# HHT_CAL_PWR_3_1_20170407.net
KiCad netlist of a schematic drawn in Altium Designer
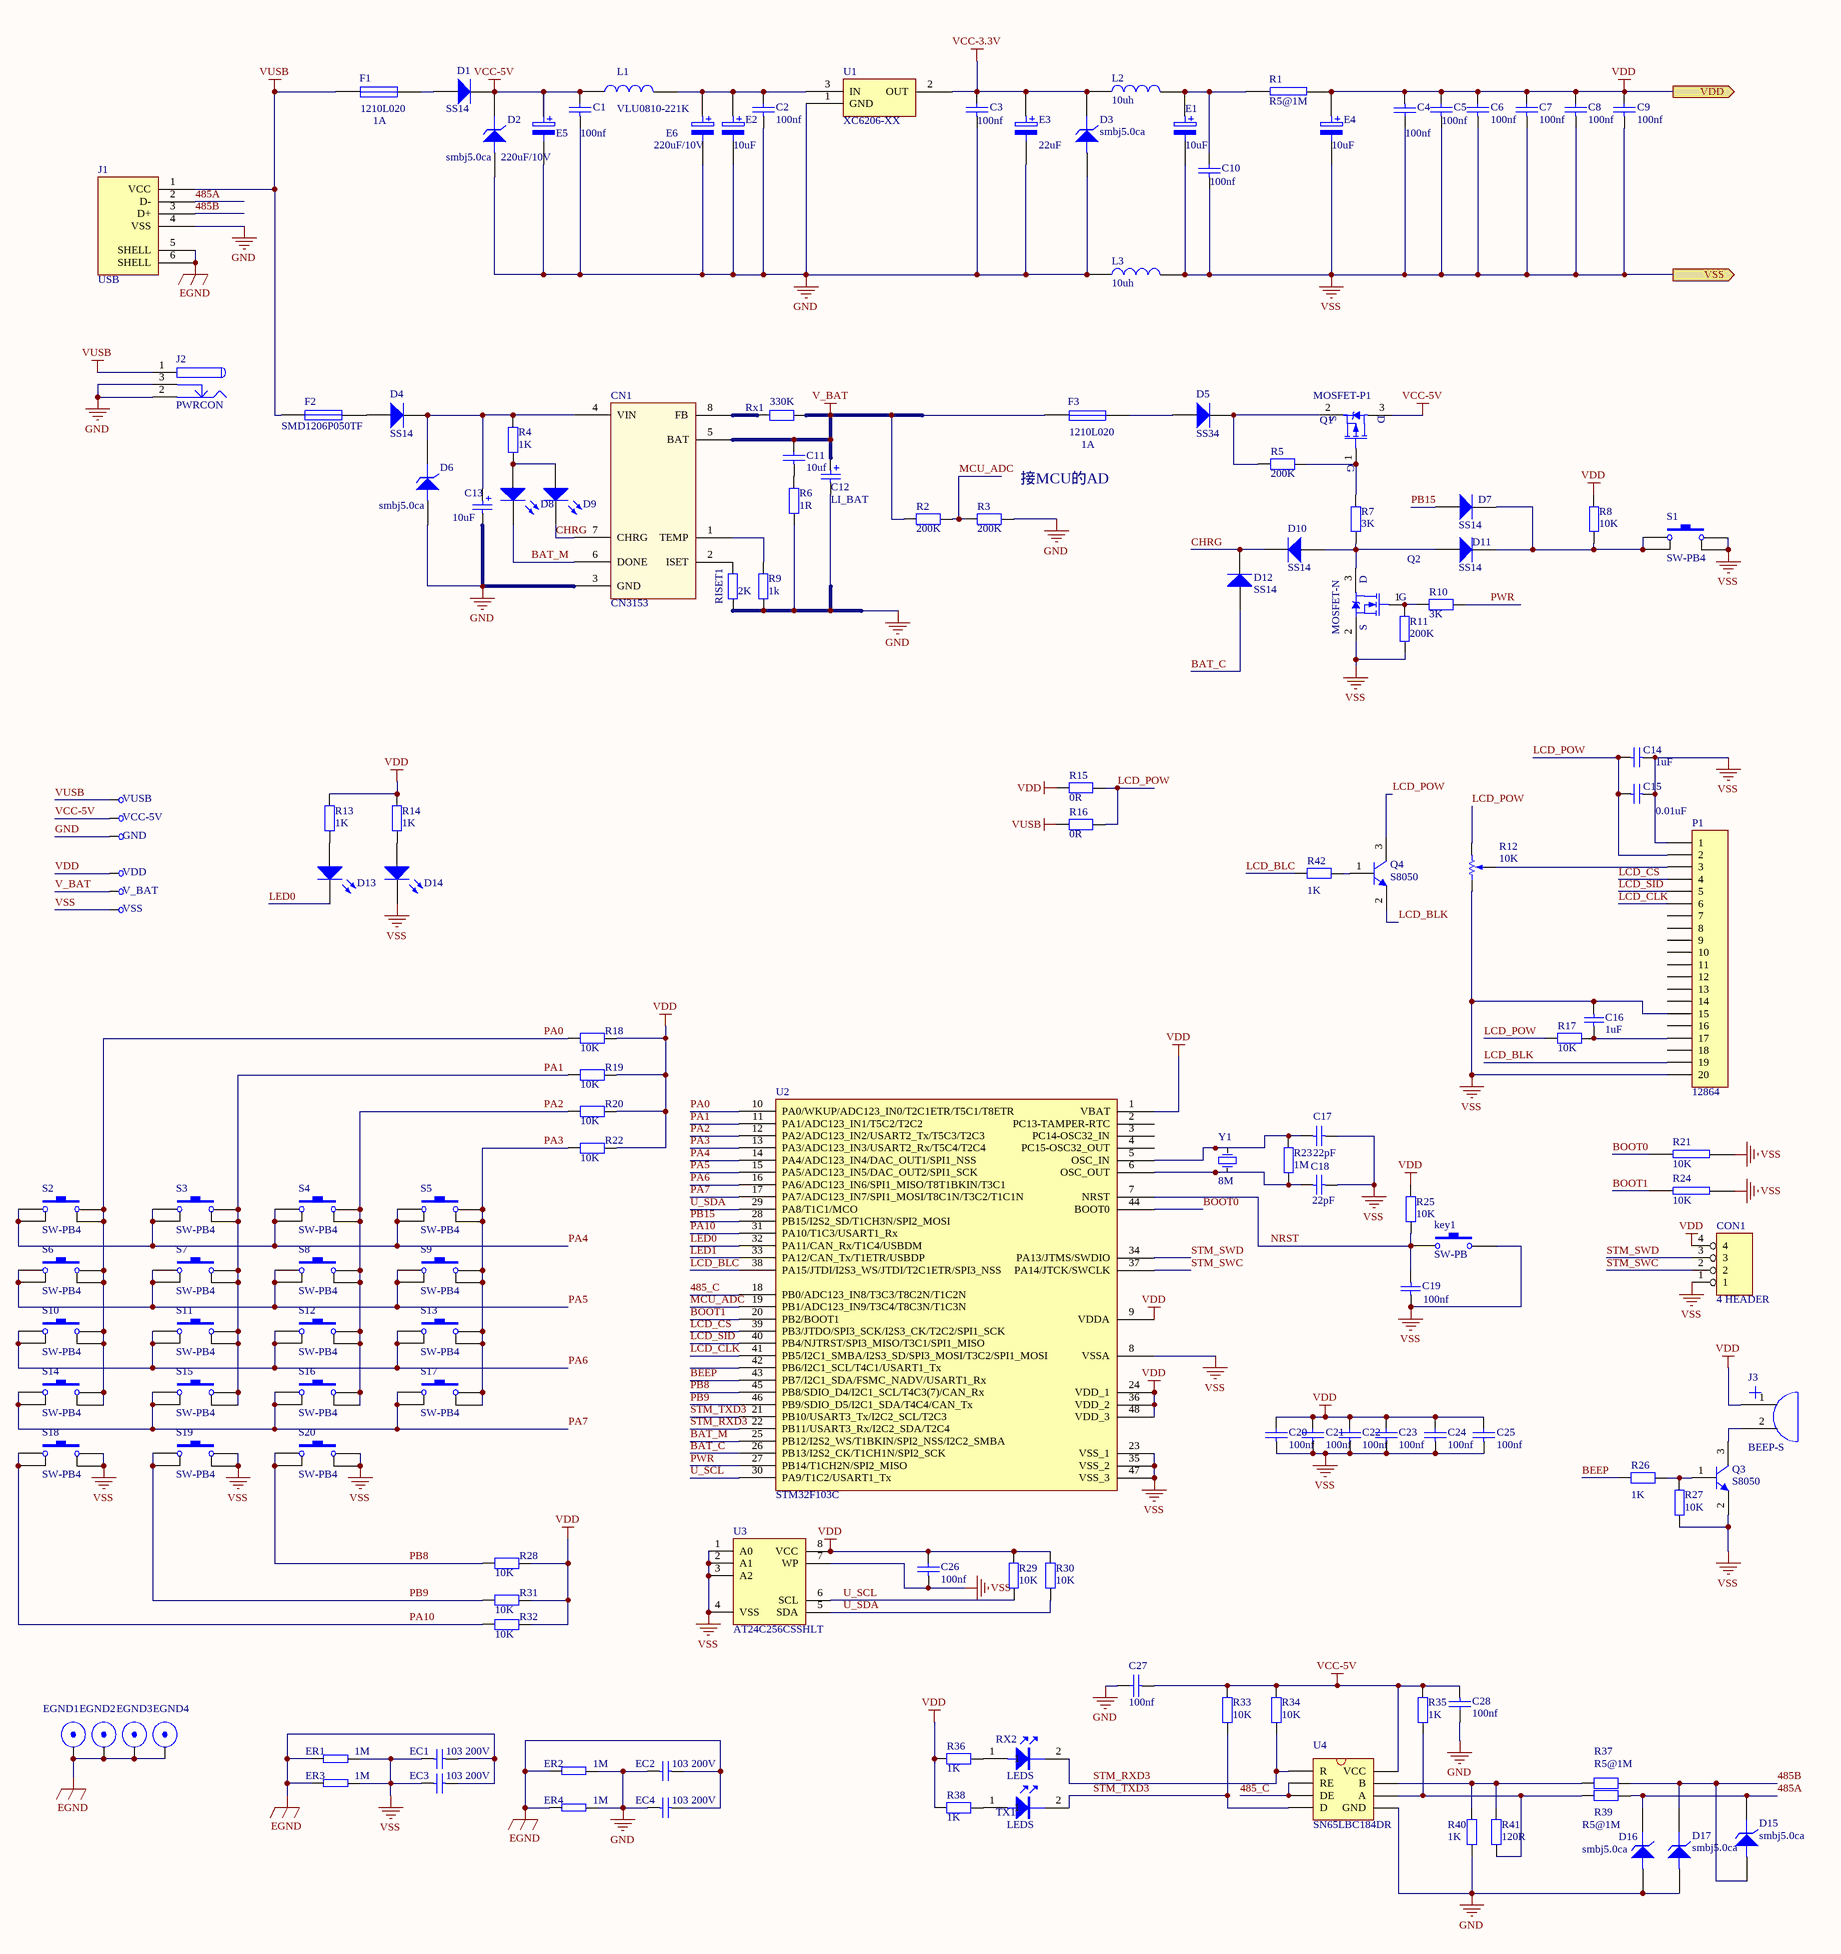
[diagram p0: HHT_CAL_PWR_3.1_20170407.SchDoc]

(export (version "E")
  (design (tool "Eeschema 10.0.6"))
  (components
    (comp (ref "C1")
      (value "100nf")
      (footprint "LC-0805_C")
      (description "Capacitor")
      (libsource (lib "Miscellaneous Devices") (part "CAP"))
    )
    (comp (ref "C2")
      (value "100nf")
      (footprint "LC-0603_C")
      (description "Capacitor")
      (libsource (lib "Miscellaneous Devices") (part "CAP"))
    )
    (comp (ref "C3")
      (value "100nf")
      (footprint "LC-0603_C")
      (description "Capacitor")
      (libsource (lib "Miscellaneous Devices") (part "CAP"))
    )
    (comp (ref "C4")
      (value "100nf")
      (footprint "LC-0603_C")
      (description "Capacitor")
      (libsource (lib "Miscellaneous Devices") (part "CAP"))
    )
    (comp (ref "C5")
      (value "100nf")
      (footprint "LC-0603_C")
      (description "Capacitor")
      (libsource (lib "Miscellaneous Devices") (part "CAP"))
    )
    (comp (ref "C6")
      (value "100nf")
      (footprint "LC-0603_C")
      (description "Capacitor")
      (libsource (lib "Miscellaneous Devices") (part "CAP"))
    )
    (comp (ref "C7")
      (value "100nf")
      (footprint "LC-0603_C")
      (description "Capacitor")
      (libsource (lib "Miscellaneous Devices") (part "CAP"))
    )
    (comp (ref "C8")
      (value "100nf")
      (footprint "LC-0603_C")
      (description "Capacitor")
      (libsource (lib "Miscellaneous Devices") (part "CAP"))
    )
    (comp (ref "C9")
      (value "100nf")
      (footprint "LC-0603_C")
      (description "Capacitor")
      (libsource (lib "Miscellaneous Devices") (part "CAP"))
    )
    (comp (ref "C10")
      (value "100nf")
      (footprint "LC-0603_C")
      (description "Capacitor")
      (libsource (lib "Miscellaneous Devices") (part "CAP"))
    )
    (comp (ref "C11")
      (value "10uf")
      (footprint "LC-CASE-A_3216")
      (description "Capacitor")
      (libsource (lib "Miscellaneous Devices") (part "CAP"))
    )
    (comp (ref "C12")
      (value "LI_BAT")
      (footprint "HDR2X1-2.54")
      (description "Polarized Capacitor (Radial)")
      (fields (field (name "PUBLISHER") "Altium Limited"))
      (libsource (lib "Miscellaneous Devices") (part "Cap Pol1"))
    )
    (comp (ref "C13")
      (value "10uF")
      (footprint "LC-CASE-B_3528")
      (description "Polarized Capacitor (Radial)")
      (fields (field (name "Comment") "100uF") (field (name "PUBLISHER") "Altium Limited"))
      (libsource (lib "Miscellaneous Devices") (part "Cap Pol1"))
    )
    (comp (ref "C14")
      (value "1uF")
      (footprint "LC-0603_C")
      (description "贴片瓷片电容")
      (fields (field (name "Comment") "1uf") (field (name "PUBLISHER") "Altium Limited"))
      (libsource (lib "fszhang") (part "Cap-S"))
    )
    (comp (ref "C15")
      (value "0.01uF")
      (footprint "LC-0603_C")
      (description "贴片瓷片电容")
      (fields (field (name "PUBLISHER") "Altium Limited"))
      (libsource (lib "fszhang") (part "Cap-S"))
    )
    (comp (ref "C16")
      (value "1uF")
      (footprint "LC-0603_C")
      (description "贴片瓷片电容")
      (fields (field (name "PUBLISHER") "Altium Limited"))
      (libsource (lib "fszhang") (part "Cap-S"))
    )
    (comp (ref "C17")
      (value "22pF")
      (footprint "LC-0603_C")
      (description "贴片瓷片电容")
      (fields (field (name "Comment") "22PF") (field (name "PUBLISHER") "Altium Limited"))
      (libsource (lib "fszhang") (part "Cap-S"))
    )
    (comp (ref "C18")
      (value "22pF")
      (footprint "LC-0603_C")
      (description "贴片瓷片电容")
      (fields (field (name "Comment") "22PF") (field (name "PUBLISHER") "Altium Limited"))
      (libsource (lib "fszhang") (part "Cap-S"))
    )
    (comp (ref "C19")
      (value "100nf")
      (footprint "LC-0603_C")
      (description "Capacitor")
      (fields (field (name "PUBLISHER") "Altium Limited"))
      (libsource (lib "Miscellaneous Devices") (part "Cap"))
    )
    (comp (ref "C20")
      (value "100nf")
      (footprint "LC-0603_C")
      (description "Capacitor")
      (libsource (lib "Miscellaneous Devices") (part "CAP"))
    )
    (comp (ref "C21")
      (value "100nf")
      (footprint "LC-0603_C")
      (description "Capacitor")
      (libsource (lib "Miscellaneous Devices") (part "CAP"))
    )
    (comp (ref "C22")
      (value "100nf")
      (footprint "LC-0603_C")
      (description "Capacitor")
      (libsource (lib "Miscellaneous Devices") (part "CAP"))
    )
    (comp (ref "C23")
      (value "100nf")
      (footprint "LC-0603_C")
      (description "Capacitor")
      (libsource (lib "Miscellaneous Devices") (part "CAP"))
    )
    (comp (ref "C24")
      (value "100nf")
      (footprint "LC-0603_C")
      (description "Capacitor")
      (libsource (lib "Miscellaneous Devices") (part "CAP"))
    )
    (comp (ref "C25")
      (value "100nf")
      (footprint "LC-0603_C")
      (description "Capacitor")
      (libsource (lib "Miscellaneous Devices") (part "CAP"))
    )
    (comp (ref "C26")
      (value "100nf")
      (footprint "LC-0603_C")
      (description "Capacitor")
      (libsource (lib "Miscellaneous Devices") (part "CAP"))
    )
    (comp (ref "C27")
      (value "100nf")
      (footprint "LC-0603_C")
      (description "Capacitor")
      (libsource (lib "Miscellaneous Devices") (part "CAP"))
    )
    (comp (ref "C28")
      (value "100nf")
      (footprint "LC-0603_C")
      (description "Capacitor")
      (libsource (lib "Miscellaneous Devices") (part "CAP"))
    )
    (comp (ref "CN1") (value "CN3153") (footprint "SOIC8") (libsource (lib "PCB_Project1") (part "CN3153")))
    (comp (ref "CON1")
      (value "4 HEADER")
      (footprint "sip4")
      (description "4 Pin Header")
      (libsource (lib "Miscellaneous Devices") (part "4 HEADER"))
    )
    (comp (ref "D1")
      (value "SS14")
      (footprint "LC-SMA(DO-214AC)_S5")
      (description "整流二极管")
      (fields (field (name "PUBLISHER") "Altium Limited"))
      (libsource (lib "fszhang") (part "Diode-R"))
    )
    (comp (ref "D2")
      (value "smbj5.0ca")
      (footprint "LC-SMB(DO-214AA)_S1")
      (description "Zener Diode")
      (libsource (lib "Miscellaneous Devices") (part "ZENER3"))
    )
    (comp (ref "D3")
      (value "smbj5.0ca")
      (footprint "LC-SMB(DO-214AA)_S1")
      (description "Zener Diode")
      (libsource (lib "Miscellaneous Devices") (part "ZENER3"))
    )
    (comp (ref "D4")
      (value "SS14")
      (footprint "LC-SMA(DO-214AC)_S5")
      (description "Default Diode")
      (fields (field (name "PUBLISHER") "Altium Limited"))
      (libsource (lib "Miscellaneous Devices") (part "Diode"))
    )
    (comp (ref "D5")
      (value "SS34")
      (footprint "LC-SMA(DO-214AC)_S5")
      (description "Default Diode")
      (fields (field (name "PUBLISHER") "Altium Limited"))
      (libsource (lib "Miscellaneous Devices") (part "Diode"))
    )
    (comp (ref "D6")
      (value "smbj5.0ca")
      (footprint "LC-SMA(DO-214AC)_S5")
      (description "Zener Diode")
      (libsource (lib "Miscellaneous Devices") (part "ZENER3"))
    )
    (comp (ref "D7")
      (value "SS14")
      (footprint "LC-SMA(DO-214AC)_S5")
      (description "Default Diode")
      (fields (field (name "PUBLISHER") "Altium Limited"))
      (libsource (lib "Miscellaneous Devices") (part "Diode"))
    )
    (comp (ref "D8")
      (value "LED0")
      (footprint "LED-0805")
      (description "发光二极管")
      (fields (field (name "PUBLISHER") "Altium Limited"))
      (libsource (lib "fszhang") (part "LED0"))
    )
    (comp (ref "D9")
      (value "LED0")
      (footprint "LED-0805")
      (description "发光二极管")
      (fields (field (name "PUBLISHER") "Altium Limited"))
      (libsource (lib "fszhang") (part "LED0"))
    )
    (comp (ref "D10")
      (value "SS14")
      (footprint "LC-SMA(DO-214AC)_S5")
      (description "Default Diode")
      (fields (field (name "PUBLISHER") "Altium Limited"))
      (libsource (lib "Miscellaneous Devices") (part "Diode"))
    )
    (comp (ref "D11")
      (value "SS14")
      (footprint "LC-SMA(DO-214AC)_S5")
      (description "Default Diode")
      (fields (field (name "PUBLISHER") "Altium Limited"))
      (libsource (lib "Miscellaneous Devices") (part "Diode"))
    )
    (comp (ref "D12")
      (value "SS14")
      (footprint "LC-SMA(DO-214AC)_S5")
      (description "Default Diode")
      (fields (field (name "PUBLISHER") "Altium Limited"))
      (libsource (lib "Miscellaneous Devices") (part "Diode"))
    )
    (comp (ref "D13")
      (value "LED0")
      (footprint "LC-0805_LED_S1")
      (description "发光二极管")
      (fields (field (name "PUBLISHER") "Altium Limited"))
      (libsource (lib "fszhang") (part "LED0"))
    )
    (comp (ref "D14")
      (value "LED0")
      (footprint "LC-0805_LED_S1")
      (description "发光二极管")
      (fields (field (name "PUBLISHER") "Altium Limited"))
      (libsource (lib "fszhang") (part "LED0"))
    )
    (comp (ref "D15")
      (value "smbj5.0ca")
      (footprint "LC-SMB(DO-214AA)_S1")
      (description "Zener Diode")
      (libsource (lib "Miscellaneous Devices") (part "ZENER3"))
    )
    (comp (ref "D16")
      (value "smbj5.0ca")
      (footprint "LC-SMB(DO-214AA)_S1")
      (description "Zener Diode")
      (libsource (lib "Miscellaneous Devices") (part "ZENER3"))
    )
    (comp (ref "D17")
      (value "smbj5.0ca")
      (footprint "LC-SMB(DO-214AA)_S1")
      (description "Zener Diode")
      (libsource (lib "Miscellaneous Devices") (part "ZENER3"))
    )
    (comp (ref "E1")
      (value "10uF")
      (footprint "LC-CASE-A_3216")
      (description "Electrolytic Capacitor")
      (libsource (lib "Miscellaneous Devices") (part "ELECTRO2"))
    )
    (comp (ref "E2")
      (value "10uF")
      (footprint "LC-CASE-B_3528")
      (description "Electrolytic Capacitor")
      (libsource (lib "Miscellaneous Devices") (part "ELECTRO2"))
    )
    (comp (ref "E3")
      (value "22uF")
      (footprint "HONOR_63X54")
      (description "Electrolytic Capacitor")
      (libsource (lib "Miscellaneous Devices") (part "ELECTRO2"))
    )
    (comp (ref "E4")
      (value "10uF")
      (footprint "LC-CASE-A_3216")
      (description "Electrolytic Capacitor")
      (libsource (lib "Miscellaneous Devices") (part "ELECTRO2"))
    )
    (comp (ref "E5")
      (value "220uF/10V")
      (footprint "HONOR_63X54")
      (description "Electrolytic Capacitor")
      (libsource (lib "Miscellaneous Devices") (part "ELECTRO2"))
    )
    (comp (ref "E6")
      (value "220uF/10V")
      (footprint "HONOR_63X54")
      (description "Electrolytic Capacitor")
      (libsource (lib "Miscellaneous Devices") (part "ELECTRO2"))
    )
    (comp (ref "EC1")
      (value "103 200V")
      (footprint "LC-1206_C")
      (description "Capacitor")
      (fields (field (name "PUBLISHER") "Altium Limited"))
      (libsource (lib "Miscellaneous Devices") (part "Cap"))
    )
    (comp (ref "EC2")
      (value "103 200V")
      (footprint "LC-1206_C")
      (description "Capacitor")
      (fields (field (name "PUBLISHER") "Altium Limited"))
      (libsource (lib "Miscellaneous Devices") (part "Cap"))
    )
    (comp (ref "EC3")
      (value "103 200V")
      (footprint "LC-1206_C")
      (description "Capacitor")
      (fields (field (name "PUBLISHER") "Altium Limited"))
      (libsource (lib "Miscellaneous Devices") (part "Cap"))
    )
    (comp (ref "EC4")
      (value "103 200V")
      (footprint "LC-1206_C")
      (description "Capacitor")
      (fields (field (name "PUBLISHER") "Altium Limited"))
      (libsource (lib "Miscellaneous Devices") (part "Cap"))
    )
    (comp (ref "EGND1")
      (value "EGND")
      (footprint "H-6-3.2m")
      (libsource (lib "PCB_Project_11") (part "EGND"))
    )
    (comp (ref "EGND2")
      (value "EGND")
      (footprint "H-6-3.2m")
      (libsource (lib "PCB_Project_11") (part "EGND"))
    )
    (comp (ref "EGND3")
      (value "EGND")
      (footprint "H-6-3.2m")
      (libsource (lib "PCB_Project_11") (part "EGND"))
    )
    (comp (ref "EGND4")
      (value "EGND")
      (footprint "H-6-3.2m")
      (libsource (lib "PCB_Project_11") (part "EGND"))
    )
    (comp (ref "ER1") (value "1M") (footprint "LC-1206_R") (libsource (lib "*") (part "RES2")))
    (comp (ref "ER2") (value "1M") (footprint "LC-1206_R") (libsource (lib "*") (part "RES2")))
    (comp (ref "ER3") (value "1M") (footprint "LC-1206_R") (libsource (lib "*") (part "RES2")))
    (comp (ref "ER4") (value "1M") (footprint "LC-1206_R") (libsource (lib "*") (part "RES2")))
    (comp (ref "F1")
      (value "1210L020")
      (footprint "LC-0805_R")
      (description "保险丝")
      (fields (field (name "ALTIUM_VALUE") "1A"))
      (libsource (lib "SCH_Footp1_Lian") (part "Fuse1"))
    )
    (comp (ref "F2")
      (value "SMD1206P050TF")
      (footprint "LC-1206_R")
      (description "Fuse")
      (fields (field (name "PUBLISHER") "Altium Limited"))
      (libsource (lib "Miscellaneous Devices") (part "Fuse 1"))
    )
    (comp (ref "F3")
      (value "1210L020")
      (footprint "LC-0805_R")
      (description "保险丝")
      (fields (field (name "ALTIUM_VALUE") "1A"))
      (libsource (lib "SCH_Footp1_Lian") (part "Fuse1"))
    )
    (comp (ref "GND")
      (value "CHECK")
      (footprint "CHECK-B")
      (description "测试点")
      (libsource (lib "fszhang") (part "CHECK"))
    )
    (comp (ref "J1")
      (value "USB")
      (footprint "USB-4-A")
      (description "USB接口")
      (libsource (lib "HDR_fszhang") (part "USB"))
    )
    (comp (ref "J2")
      (value "PWRCON")
      (footprint "DC-005")
      (description "直流电源端子")
      (fields (field (name "PUBLISHER") "Altium Limited"))
      (libsource (lib "HDR_fszhang") (part "PWRCON"))
    )
    (comp (ref "J3")
      (value "BEEP-S")
      (footprint "BEEP-S")
      (description "有源蜂鸣器")
      (libsource (lib "fszhang") (part "BEEP-S"))
    )
    (comp (ref "key1")
      (value "SW-PB")
      (footprint "SW_PB2_C1")
      (description "微动开关")
      (fields (field (name "PUBLISHER") "Altium Limited"))
      (libsource (lib "Fszhang") (part "SW-PB"))
    )
    (comp (ref "L1")
      (value "VLU0810-221K")
      (footprint "L-SMD-7")
      (libsource (lib "Miscellaneous Devices") (part "INDUCTOR"))
    )
    (comp (ref "L2")
      (value "10uh")
      (footprint "LC-0805_L")
      (libsource (lib "Miscellaneous Devices") (part "INDUCTOR"))
    )
    (comp (ref "L3")
      (value "10uh")
      (footprint "LC-0805_L")
      (libsource (lib "Miscellaneous Devices") (part "INDUCTOR"))
    )
    (comp (ref "P1")
      (value "12864")
      (footprint "HDR1X20")
      (description "Header, 20-Pin")
      (fields (field (name "PUBLISHER") "Altium Limited"))
      (libsource (lib "Miscellaneous Connectors") (part "Header 20"))
    )
    (comp (ref "Q1") (value "MOSFET-P1") (footprint "SOT23-3") (libsource (lib "fszhang") (part "MOSFET-P1")))
    (comp (ref "Q2")
      (value "MOSFET-N")
      (footprint "LC-SOT-23(SOT-23-3)")
      (description "N-Channel MOSFET")
      (fields (field (name "PUBLISHER") "Altium Limited"))
      (libsource (lib "fszhang") (part "MOSFET-N"))
    )
    (comp (ref "Q3")
      (value "S8050")
      (footprint "SOT23-3")
      (description "贴片三极管")
      (fields (field (name "PUBLISHER") "Altium Limited"))
      (libsource (lib "fszhang") (part "NPN1"))
    )
    (comp (ref "Q4")
      (value "S8050")
      (footprint "SOT23-3")
      (description "贴片三极管")
      (fields (field (name "PUBLISHER") "Altium Limited"))
      (libsource (lib "fszhang") (part "NPN1"))
    )
    (comp (ref "R1")
      (value "R5@1M")
      (footprint "LC-0805_R")
      (libsource (lib "Miscellaneous Devices") (part "RES2"))
    )
    (comp (ref "R2")
      (value "200K")
      (footprint "LC-0603_R")
      (description "Resistor")
      (fields (field (name "PUBLISHER") "Altium Limited"))
      (libsource (lib "") (part "Res2_1"))
    )
    (comp (ref "R3")
      (value "200K")
      (footprint "LC-0603_R")
      (description "Resistor")
      (fields (field (name "PUBLISHER") "Altium Limited"))
      (libsource (lib "") (part "Res2_1"))
    )
    (comp (ref "R4")
      (value "1K")
      (footprint "LC-0603_R")
      (description "Resistor")
      (fields (field (name "PUBLISHER") "Altium Limited"))
      (libsource (lib "") (part "Res2_2"))
    )
    (comp (ref "R5")
      (value "200K")
      (footprint "LC-0603_R")
      (description "Resistor")
      (fields (field (name "PUBLISHER") "Altium Limited"))
      (libsource (lib "") (part "Res2_1"))
    )
    (comp (ref "R6")
      (value "1R")
      (footprint "LC-0603_R")
      (description "Resistor")
      (fields (field (name "PUBLISHER") "Altium Limited"))
      (libsource (lib "Miscellaneous Devices") (part "Res2"))
    )
    (comp (ref "R7")
      (value "3K")
      (footprint "LC-0603_R")
      (description "Resistor")
      (fields (field (name "PUBLISHER") "Altium Limited"))
      (libsource (lib "") (part "Res2_2"))
    )
    (comp (ref "R8")
      (value "10K")
      (footprint "LC-0603_R")
      (description "贴片电阻")
      (fields (field (name "PUBLISHER") "Altium Limited"))
      (libsource (lib "fszhang") (part "Res1"))
    )
    (comp (ref "R9")
      (value "1k")
      (footprint "LC-0603_R")
      (description "Resistor")
      (fields (field (name "PUBLISHER") "Altium Limited"))
      (libsource (lib "Miscellaneous Devices") (part "Res2"))
    )
    (comp (ref "R10")
      (value "3K")
      (footprint "LC-0603_R")
      (description "Resistor")
      (fields (field (name "PUBLISHER") "Altium Limited"))
      (libsource (lib "") (part "Res2_3"))
    )
    (comp (ref "R11")
      (value "200K")
      (footprint "LC-0603_R")
      (description "Resistor")
      (fields (field (name "PUBLISHER") "Altium Limited"))
      (libsource (lib "") (part "Res2_2"))
    )
    (comp (ref "R12")
      (value "10K")
      (footprint "VR-3296W")
      (description "精密可调电阻")
      (fields (field (name "Comment") "RPot") (field (name "PUBLISHER") "Altium Limited"))
      (libsource (lib "fszhang") (part "RPot"))
    )
    (comp (ref "R13")
      (value "1K")
      (footprint "0805-1")
      (description "贴片电阻")
      (fields (field (name "PUBLISHER") "Altium Limited"))
      (libsource (lib "fszhang") (part "Res1"))
    )
    (comp (ref "R14")
      (value "1K")
      (footprint "0805-1")
      (description "贴片电阻")
      (fields (field (name "PUBLISHER") "Altium Limited"))
      (libsource (lib "fszhang") (part "Res1"))
    )
    (comp (ref "R15")
      (value "0R")
      (footprint "LC-0805_R")
      (description "贴片电阻")
      (fields (field (name "PUBLISHER") "Altium Limited"))
      (libsource (lib "") (part "Res1_1"))
    )
    (comp (ref "R16")
      (value "0R")
      (footprint "LC-0805_R")
      (description "贴片电阻")
      (fields (field (name "PUBLISHER") "Altium Limited"))
      (libsource (lib "") (part "Res1_1"))
    )
    (comp (ref "R17")
      (value "10K")
      (footprint "0603-1")
      (description "贴片电阻")
      (fields (field (name "PUBLISHER") "Altium Limited"))
      (libsource (lib "") (part "Res1_1"))
    )
    (comp (ref "R18")
      (value "10K")
      (footprint "LC-0603_R")
      (description "贴片电阻")
      (fields (field (name "PUBLISHER") "Altium Limited"))
      (libsource (lib "") (part "Res1_1"))
    )
    (comp (ref "R19")
      (value "10K")
      (footprint "LC-0603_R")
      (description "贴片电阻")
      (fields (field (name "PUBLISHER") "Altium Limited"))
      (libsource (lib "") (part "Res1_1"))
    )
    (comp (ref "R20")
      (value "10K")
      (footprint "LC-0603_R")
      (description "贴片电阻")
      (fields (field (name "PUBLISHER") "Altium Limited"))
      (libsource (lib "") (part "Res1_1"))
    )
    (comp (ref "R21")
      (value "10K")
      (footprint "LC-0603_R")
      (libsource (lib "Miscellaneous Devices") (part "RES2"))
    )
    (comp (ref "R22")
      (value "10K")
      (footprint "LC-0603_R")
      (description "贴片电阻")
      (fields (field (name "PUBLISHER") "Altium Limited"))
      (libsource (lib "") (part "Res1_1"))
    )
    (comp (ref "R23")
      (value "1M")
      (footprint "0603-1")
      (description "贴片电阻")
      (fields (field (name "PUBLISHER") "Altium Limited"))
      (libsource (lib "fszhang") (part "Res1"))
    )
    (comp (ref "R24")
      (value "10K")
      (footprint "LC-0603_R")
      (libsource (lib "Miscellaneous Devices") (part "RES2"))
    )
    (comp (ref "R25")
      (value "10K")
      (footprint "LC-0603_R")
      (description "Resistor")
      (fields (field (name "PUBLISHER") "Altium Limited"))
      (libsource (lib "") (part "Res2_2"))
    )
    (comp (ref "R26")
      (value "1K")
      (footprint "LC-0603_R")
      (description "贴片电阻")
      (fields (field (name "PUBLISHER") "Altium Limited"))
      (libsource (lib "") (part "Res1_1"))
    )
    (comp (ref "R27")
      (value "10K")
      (footprint "LC-0603_R")
      (description "贴片电阻")
      (fields (field (name "Comment") "10k") (field (name "PUBLISHER") "Altium Limited"))
      (libsource (lib "fszhang") (part "Res1"))
    )
    (comp (ref "R28")
      (value "10K")
      (footprint "LC-0603_R")
      (description "贴片电阻")
      (fields (field (name "PUBLISHER") "Altium Limited"))
      (libsource (lib "") (part "Res1_1"))
    )
    (comp (ref "R29")
      (value "10K")
      (footprint "LC-0603_R")
      (description "Resistor")
      (fields (field (name "PUBLISHER") "Altium Limited"))
      (libsource (lib "Miscellaneous Devices") (part "Res2"))
    )
    (comp (ref "R30")
      (value "10K")
      (footprint "LC-0603_R")
      (description "Resistor")
      (fields (field (name "PUBLISHER") "Altium Limited"))
      (libsource (lib "Miscellaneous Devices") (part "Res2"))
    )
    (comp (ref "R31")
      (value "10K")
      (footprint "LC-0603_R")
      (description "贴片电阻")
      (fields (field (name "PUBLISHER") "Altium Limited"))
      (libsource (lib "") (part "Res1_1"))
    )
    (comp (ref "R32")
      (value "10K")
      (footprint "LC-0603_R")
      (description "贴片电阻")
      (fields (field (name "PUBLISHER") "Altium Limited"))
      (libsource (lib "") (part "Res1_1"))
    )
    (comp (ref "R33")
      (value "10K")
      (footprint "LC-0603_r")
      (description "Resistor")
      (fields (field (name "PUBLISHER") "Altium Limited"))
      (libsource (lib "") (part "Res2_2"))
    )
    (comp (ref "R34")
      (value "10K")
      (footprint "LC-0603_r")
      (description "Resistor")
      (fields (field (name "PUBLISHER") "Altium Limited"))
      (libsource (lib "") (part "Res2_2"))
    )
    (comp (ref "R35")
      (value "1K")
      (footprint "LC-0603_R")
      (description "Resistor")
      (fields (field (name "PUBLISHER") "Altium Limited"))
      (libsource (lib "") (part "Res2_2"))
    )
    (comp (ref "R36")
      (value "1K")
      (footprint "LC-0603_R")
      (description "Resistor")
      (fields (field (name "PUBLISHER") "Altium Limited"))
      (libsource (lib "") (part "Res2_1"))
    )
    (comp (ref "R37")
      (value "R5@1M")
      (footprint "LC-0805_R")
      (description "Resistor")
      (fields (field (name "PUBLISHER") "Altium Limited"))
      (libsource (lib "") (part "Res2_3"))
    )
    (comp (ref "R38")
      (value "1K")
      (footprint "LC-0603_R")
      (description "Resistor")
      (fields (field (name "PUBLISHER") "Altium Limited"))
      (libsource (lib "") (part "Res2_1"))
    )
    (comp (ref "R39")
      (value "R5@1M")
      (footprint "LC-0805_R")
      (description "Resistor")
      (fields (field (name "PUBLISHER") "Altium Limited"))
      (libsource (lib "") (part "Res2_3"))
    )
    (comp (ref "R40")
      (value "1K")
      (footprint "LC-0603_R")
      (description "Resistor")
      (fields (field (name "PUBLISHER") "Altium Limited"))
      (libsource (lib "") (part "Res2_2"))
    )
    (comp (ref "R41")
      (value "120R")
      (footprint "LC-0603_R")
      (description "Resistor")
      (fields (field (name "PUBLISHER") "Altium Limited"))
      (libsource (lib "") (part "Res2_2"))
    )
    (comp (ref "R42")
      (value "1K")
      (footprint "LC-0603_R")
      (description "贴片电阻")
      (fields (field (name "PUBLISHER") "Altium Limited"))
      (libsource (lib "") (part "Res1_1"))
    )
    (comp (ref "RISET1")
      (value "2K")
      (footprint "LC-0603_R")
      (description "Resistor")
      (fields (field (name "PUBLISHER") "Altium Limited"))
      (libsource (lib "Miscellaneous Devices") (part "Res2"))
    )
    (comp (ref "Rx1")
      (value "330K")
      (footprint "LC-0603_R")
      (description "Resistor")
      (fields (field (name "PUBLISHER") "Altium Limited"))
      (libsource (lib "") (part "Res2_3"))
    )
    (comp (ref "RX2")
      (value "LEDS")
      (footprint "LC-0805_LED_S1")
      (libsource (lib "SCH_Footp1_Lian") (part "LEDS"))
    )
    (comp (ref "S1")
      (value "SW-PB4")
      (footprint "金属轻触开关")
      (description "微动开关")
      (fields (field (name "PUBLISHER") "Altium Limited"))
      (libsource (lib "fszhang") (part "SW-PB4"))
    )
    (comp (ref "S2")
      (value "SW-PB4")
      (footprint "金属轻触开关")
      (description "微动开关")
      (fields (field (name "PUBLISHER") "Altium Limited"))
      (libsource (lib "fszhang") (part "SW-PB4"))
    )
    (comp (ref "S3")
      (value "SW-PB4")
      (footprint "金属轻触开关")
      (description "微动开关")
      (fields (field (name "PUBLISHER") "Altium Limited"))
      (libsource (lib "fszhang") (part "SW-PB4"))
    )
    (comp (ref "S4")
      (value "SW-PB4")
      (footprint "金属轻触开关")
      (description "微动开关")
      (fields (field (name "PUBLISHER") "Altium Limited"))
      (libsource (lib "fszhang") (part "SW-PB4"))
    )
    (comp (ref "S5")
      (value "SW-PB4")
      (footprint "金属轻触开关")
      (description "微动开关")
      (fields (field (name "PUBLISHER") "Altium Limited"))
      (libsource (lib "fszhang") (part "SW-PB4"))
    )
    (comp (ref "S6")
      (value "SW-PB4")
      (footprint "金属轻触开关")
      (description "微动开关")
      (fields (field (name "PUBLISHER") "Altium Limited"))
      (libsource (lib "fszhang") (part "SW-PB4"))
    )
    (comp (ref "S7")
      (value "SW-PB4")
      (footprint "金属轻触开关")
      (description "微动开关")
      (fields (field (name "PUBLISHER") "Altium Limited"))
      (libsource (lib "fszhang") (part "SW-PB4"))
    )
    (comp (ref "S8")
      (value "SW-PB4")
      (footprint "金属轻触开关")
      (description "微动开关")
      (fields (field (name "PUBLISHER") "Altium Limited"))
      (libsource (lib "fszhang") (part "SW-PB4"))
    )
    (comp (ref "S9")
      (value "SW-PB4")
      (footprint "金属轻触开关")
      (description "微动开关")
      (fields (field (name "PUBLISHER") "Altium Limited"))
      (libsource (lib "fszhang") (part "SW-PB4"))
    )
    (comp (ref "S10")
      (value "SW-PB4")
      (footprint "金属轻触开关")
      (description "微动开关")
      (fields (field (name "PUBLISHER") "Altium Limited"))
      (libsource (lib "fszhang") (part "SW-PB4"))
    )
    (comp (ref "S11")
      (value "SW-PB4")
      (footprint "金属轻触开关")
      (description "微动开关")
      (fields (field (name "PUBLISHER") "Altium Limited"))
      (libsource (lib "fszhang") (part "SW-PB4"))
    )
    (comp (ref "S12")
      (value "SW-PB4")
      (footprint "金属轻触开关")
      (description "微动开关")
      (fields (field (name "PUBLISHER") "Altium Limited"))
      (libsource (lib "fszhang") (part "SW-PB4"))
    )
    (comp (ref "S13")
      (value "SW-PB4")
      (footprint "金属轻触开关")
      (description "微动开关")
      (fields (field (name "PUBLISHER") "Altium Limited"))
      (libsource (lib "fszhang") (part "SW-PB4"))
    )
    (comp (ref "S14")
      (value "SW-PB4")
      (footprint "金属轻触开关")
      (description "微动开关")
      (fields (field (name "PUBLISHER") "Altium Limited"))
      (libsource (lib "fszhang") (part "SW-PB4"))
    )
    (comp (ref "S15")
      (value "SW-PB4")
      (footprint "金属轻触开关")
      (description "微动开关")
      (fields (field (name "PUBLISHER") "Altium Limited"))
      (libsource (lib "fszhang") (part "SW-PB4"))
    )
    (comp (ref "S16")
      (value "SW-PB4")
      (footprint "金属轻触开关")
      (description "微动开关")
      (fields (field (name "PUBLISHER") "Altium Limited"))
      (libsource (lib "fszhang") (part "SW-PB4"))
    )
    (comp (ref "S17")
      (value "SW-PB4")
      (footprint "金属轻触开关")
      (description "微动开关")
      (fields (field (name "PUBLISHER") "Altium Limited"))
      (libsource (lib "fszhang") (part "SW-PB4"))
    )
    (comp (ref "S18")
      (value "SW-PB4")
      (footprint "金属轻触开关")
      (description "微动开关")
      (fields (field (name "PUBLISHER") "Altium Limited"))
      (libsource (lib "fszhang") (part "SW-PB4"))
    )
    (comp (ref "S19")
      (value "SW-PB4")
      (footprint "金属轻触开关")
      (description "微动开关")
      (fields (field (name "PUBLISHER") "Altium Limited"))
      (libsource (lib "fszhang") (part "SW-PB4"))
    )
    (comp (ref "S20")
      (value "SW-PB4")
      (footprint "金属轻触开关")
      (description "微动开关")
      (fields (field (name "PUBLISHER") "Altium Limited"))
      (libsource (lib "fszhang") (part "SW-PB4"))
    )
    (comp (ref "TX1")
      (value "LEDS")
      (footprint "LC-0805_LED_S1")
      (libsource (lib "SCH_Footp1_Lian") (part "LEDS"))
    )
    (comp (ref "U1")
      (value "XC6206-XX")
      (footprint "LC-SOT-23(SOT-23-3)")
      (libsource (lib "fszhang") (part "XC6206-XX"))
    )
    (comp (ref "U2")
      (value "STM32F103C")
      (footprint "LC-LQFP-48_7x7x05P")
      (description "STM32单片机48引脚")
      (libsource (lib "fszhang") (part "STM32F103C"))
    )
    (comp (ref "U3")
      (value "AT24C256CSSHLT")
      (footprint "SOIC-8")
      (description "EEROM存储器")
      (libsource (lib "SCH_Footp1_Lian") (part "AT24C02"))
    )
    (comp (ref "U4") (value "SN65LBC184DR") (footprint "soic-8") (libsource (lib "*") (part "75176B")))
    (comp (ref "VCC-5V")
      (value "CHECK")
      (footprint "CHECK-B")
      (description "测试点")
      (libsource (lib "fszhang") (part "CHECK"))
    )
    (comp (ref "VDD")
      (value "CHECK")
      (footprint "CHECK-B")
      (description "测试点")
      (libsource (lib "fszhang") (part "CHECK"))
    )
    (comp (ref "VSS")
      (value "CHECK")
      (footprint "CHECK-B")
      (description "测试点")
      (libsource (lib "fszhang") (part "CHECK"))
    )
    (comp (ref "VUSB")
      (value "CHECK")
      (footprint "CHECK-B")
      (description "测试点")
      (libsource (lib "fszhang") (part "CHECK"))
    )
    (comp (ref "V_BAT")
      (value "CHECK")
      (footprint "CHECK-B")
      (description "测试点")
      (libsource (lib "fszhang") (part "CHECK"))
    )
    (comp (ref "Y1")
      (value "8M")
      (footprint "X-SM49")
      (description "晶振")
      (fields (field (name "Comment") "XTAL") (field (name "PUBLISHER") "Altium Limited"))
      (libsource (lib "fszhang") (part "XTAL"))
    )
  )
  (nets
    (net (code "1") (name "/485A") (class "Default")
      (node (ref "D15") (pin "2") (pinfunction "K_2") (pintype "passive"))
      (node (ref "D16") (pin "2") (pinfunction "K_2") (pintype "passive"))
      (node (ref "J1") (pin "2") (pinfunction "D-_2") (pintype "passive"))
      (node (ref "R39") (pin "1") (pinfunction "1_1") (pintype "passive"))
    )
    (net (code "2") (name "/485B") (class "Default")
      (node (ref "D15") (pin "1") (pinfunction "A_1") (pintype "passive"))
      (node (ref "D17") (pin "2") (pinfunction "K_2") (pintype "passive"))
      (node (ref "J1") (pin "3") (pinfunction "D+_3") (pintype "passive"))
      (node (ref "R37") (pin "1") (pinfunction "1_1") (pintype "passive"))
    )
    (net (code "3") (name "/485_C") (class "Default")
      (node (ref "U2") (pin "18") (pinfunction "PB0/ADC123_IN8/T3C3/T8C2N/T1C2N_18") (pintype "passive"))
      (node (ref "U4") (pin "2") (pinfunction "RE_2") (pintype "passive"))
      (node (ref "U4") (pin "3") (pinfunction "DE_3") (pintype "passive"))
    )
    (net (code "4") (name "/BAT_C") (class "Default")
      (node (ref "D12") (pin "1") (pinfunction "A_1") (pintype "passive"))
      (node (ref "U2") (pin "26") (pinfunction "PB13/I2S2_CK/T1CH1N/SPI2_SCK_26") (pintype "passive"))
    )
    (net (code "5") (name "/BAT_M") (class "Default")
      (node (ref "CN1") (pin "6") (pinfunction "DONE_6") (pintype "passive"))
      (node (ref "D8") (pin "2") (pinfunction "K_2") (pintype "passive"))
      (node (ref "U2") (pin "25") (pinfunction "PB12/I2S2_WS/T1BKIN/SPI2_NSS/I2C2_SMBA_25") (pintype "passive"))
    )
    (net (code "6") (name "/BEEP") (class "Default")
      (node (ref "R26") (pin "1") (pinfunction "1_1") (pintype "passive"))
      (node (ref "U2") (pin "43") (pinfunction "PB7/I2C1_SDA/FSMC_NADV/USART1_Rx_43") (pintype "passive"))
    )
    (net (code "7") (name "/BOOT0") (class "Default")
      (node (ref "R21") (pin "2") (pinfunction "2_2") (pintype "passive"))
      (node (ref "U2") (pin "44") (pinfunction "BOOT0_44") (pintype "passive"))
    )
    (net (code "8") (name "/BOOT1") (class "Default")
      (node (ref "R24") (pin "2") (pinfunction "2_2") (pintype "passive"))
      (node (ref "U2") (pin "20") (pinfunction "PB2/BOOT1_20") (pintype "passive"))
    )
    (net (code "9") (name "/CHRG") (class "Default")
      (node (ref "CN1") (pin "7") (pinfunction "CHRG_7") (pintype "passive"))
      (node (ref "D10") (pin "2") (pinfunction "K_2") (pintype "passive"))
      (node (ref "D12") (pin "2") (pinfunction "K_2") (pintype "passive"))
      (node (ref "D9") (pin "2") (pinfunction "K_2") (pintype "passive"))
    )
    (net (code "10") (name "/LCD_BLC") (class "Default")
      (node (ref "R42") (pin "1") (pinfunction "1_1") (pintype "passive"))
      (node (ref "U2") (pin "38") (pinfunction "PA15/JTDI/I2S3_WS/JTDI/T2C1ETR/SPI3_NSS_38") (pintype "passive"))
    )
    (net (code "11") (name "/LCD_BLK") (class "Default")
      (node (ref "P1") (pin "19") (pinfunction "19_19") (pintype "passive"))
      (node (ref "Q4") (pin "2") (pinfunction "E_2") (pintype "passive"))
    )
    (net (code "12") (name "/LCD_CLK") (class "Default")
      (node (ref "P1") (pin "6") (pinfunction "6_6") (pintype "passive"))
      (node (ref "U2") (pin "41") (pinfunction "PB5/I2C1_SMBA/I2S3_SD/SPI3_MOSI/T3C2/SPI1_MOSI_41") (pintype "passive"))
    )
    (net (code "13") (name "/LCD_CS") (class "Default")
      (node (ref "P1") (pin "4") (pinfunction "4_4") (pintype "passive"))
      (node (ref "U2") (pin "39") (pinfunction "PB3/JTDO/SPI3_SCK/I2S3_CK/T2C2/SPI1_SCK_39") (pintype "passive"))
    )
    (net (code "14") (name "/LCD_POW") (class "Default")
      (node (ref "C14") (pin "1") (pinfunction "1_1") (pintype "passive"))
      (node (ref "C15") (pin "1") (pinfunction "1_1") (pintype "passive"))
      (node (ref "P1") (pin "2") (pinfunction "2_2") (pintype "passive"))
      (node (ref "Q4") (pin "3") (pinfunction "C_3") (pintype "passive"))
      (node (ref "R12") (pin "3") (pinfunction "BOT_3") (pintype "passive"))
      (node (ref "R15") (pin "2") (pinfunction "2_2") (pintype "passive"))
      (node (ref "R16") (pin "2") (pinfunction "2_2") (pintype "passive"))
      (node (ref "R17") (pin "1") (pinfunction "1_1") (pintype "passive"))
    )
    (net (code "15") (name "/LCD_SID") (class "Default")
      (node (ref "P1") (pin "5") (pinfunction "5_5") (pintype "passive"))
      (node (ref "U2") (pin "40") (pinfunction "PB4/NJTRST/SPI3_MISO/T3C1/SPI1_MISO_40") (pintype "passive"))
    )
    (net (code "16") (name "/LED0") (class "Default")
      (node (ref "D13") (pin "2") (pinfunction "K_2") (pintype "passive"))
      (node (ref "U2") (pin "32") (pinfunction "PA11/CAN_Rx/T1C4/USBDM_32") (pintype "passive"))
    )
    (net (code "17") (name "/LED1") (class "Default")
      (node (ref "U2") (pin "33") (pinfunction "PA12/CAN_Tx/T1ETR/USBDP_33") (pintype "passive"))
    )
    (net (code "18") (name "/MCU_ADC") (class "Default")
      (node (ref "R2") (pin "2") (pinfunction "2_2") (pintype "passive"))
      (node (ref "R3") (pin "1") (pinfunction "1_1") (pintype "passive"))
      (node (ref "U2") (pin "19") (pinfunction "PB1/ADC123_IN9/T3C4/T8C3N/T1C3N_19") (pintype "passive"))
    )
    (net (code "19") (name "/NRST") (class "Default")
      (node (ref "C19") (pin "2") (pinfunction "2_2") (pintype "passive"))
      (node (ref "R25") (pin "1") (pinfunction "1_1") (pintype "passive"))
      (node (ref "U2") (pin "7") (pinfunction "NRST_7") (pintype "passive"))
      (node (ref "key1") (pin "1") (pinfunction "1_1") (pintype "passive"))
    )
    (net (code "20") (name "/PA0") (class "Default")
      (node (ref "R18") (pin "1") (pinfunction "1_1") (pintype "passive"))
      (node (ref "S10") (pin "2") (pinfunction "2_2") (pintype "passive"))
      (node (ref "S10") (pin "3") (pinfunction "3_3") (pintype "passive"))
      (node (ref "S14") (pin "2") (pinfunction "2_2") (pintype "passive"))
      (node (ref "S14") (pin "3") (pinfunction "3_3") (pintype "passive"))
      (node (ref "S2") (pin "2") (pinfunction "2_2") (pintype "passive"))
      (node (ref "S2") (pin "3") (pinfunction "3_3") (pintype "passive"))
      (node (ref "S6") (pin "2") (pinfunction "2_2") (pintype "passive"))
      (node (ref "S6") (pin "3") (pinfunction "3_3") (pintype "passive"))
      (node (ref "U2") (pin "10") (pinfunction "PA0/WKUP/ADC123_IN0/T2C1ETR/T5C1/T8ETR_10") (pintype "passive"))
    )
    (net (code "21") (name "/PA1") (class "Default")
      (node (ref "R19") (pin "1") (pinfunction "1_1") (pintype "passive"))
      (node (ref "S11") (pin "2") (pinfunction "2_2") (pintype "passive"))
      (node (ref "S11") (pin "3") (pinfunction "3_3") (pintype "passive"))
      (node (ref "S15") (pin "2") (pinfunction "2_2") (pintype "passive"))
      (node (ref "S15") (pin "3") (pinfunction "3_3") (pintype "passive"))
      (node (ref "S3") (pin "2") (pinfunction "2_2") (pintype "passive"))
      (node (ref "S3") (pin "3") (pinfunction "3_3") (pintype "passive"))
      (node (ref "S7") (pin "2") (pinfunction "2_2") (pintype "passive"))
      (node (ref "S7") (pin "3") (pinfunction "3_3") (pintype "passive"))
      (node (ref "U2") (pin "11") (pinfunction "PA1/ADC123_IN1/T5C2/T2C2_11") (pintype "passive"))
    )
    (net (code "22") (name "/PA2") (class "Default")
      (node (ref "R20") (pin "1") (pinfunction "1_1") (pintype "passive"))
      (node (ref "S12") (pin "2") (pinfunction "2_2") (pintype "passive"))
      (node (ref "S12") (pin "3") (pinfunction "3_3") (pintype "passive"))
      (node (ref "S16") (pin "2") (pinfunction "2_2") (pintype "passive"))
      (node (ref "S16") (pin "3") (pinfunction "3_3") (pintype "passive"))
      (node (ref "S4") (pin "2") (pinfunction "2_2") (pintype "passive"))
      (node (ref "S4") (pin "3") (pinfunction "3_3") (pintype "passive"))
      (node (ref "S8") (pin "2") (pinfunction "2_2") (pintype "passive"))
      (node (ref "S8") (pin "3") (pinfunction "3_3") (pintype "passive"))
      (node (ref "U2") (pin "12") (pinfunction "PA2/ADC123_IN2/USART2_Tx/T5C3/T2C3_12") (pintype "passive"))
    )
    (net (code "23") (name "/PA3") (class "Default")
      (node (ref "R22") (pin "1") (pinfunction "1_1") (pintype "passive"))
      (node (ref "S13") (pin "2") (pinfunction "2_2") (pintype "passive"))
      (node (ref "S13") (pin "3") (pinfunction "3_3") (pintype "passive"))
      (node (ref "S17") (pin "2") (pinfunction "2_2") (pintype "passive"))
      (node (ref "S17") (pin "3") (pinfunction "3_3") (pintype "passive"))
      (node (ref "S5") (pin "2") (pinfunction "2_2") (pintype "passive"))
      (node (ref "S5") (pin "3") (pinfunction "3_3") (pintype "passive"))
      (node (ref "S9") (pin "2") (pinfunction "2_2") (pintype "passive"))
      (node (ref "S9") (pin "3") (pinfunction "3_3") (pintype "passive"))
      (node (ref "U2") (pin "13") (pinfunction "PA3/ADC123_IN3/USART2_Rx/T5C4/T2C4_13") (pintype "passive"))
    )
    (net (code "24") (name "/PA4") (class "Default")
      (node (ref "S2") (pin "1") (pinfunction "1_1") (pintype "passive"))
      (node (ref "S2") (pin "4") (pinfunction "4_4") (pintype "passive"))
      (node (ref "S3") (pin "1") (pinfunction "1_1") (pintype "passive"))
      (node (ref "S3") (pin "4") (pinfunction "4_4") (pintype "passive"))
      (node (ref "S4") (pin "1") (pinfunction "1_1") (pintype "passive"))
      (node (ref "S4") (pin "4") (pinfunction "4_4") (pintype "passive"))
      (node (ref "S5") (pin "1") (pinfunction "1_1") (pintype "passive"))
      (node (ref "S5") (pin "4") (pinfunction "4_4") (pintype "passive"))
      (node (ref "U2") (pin "14") (pinfunction "PA4/ADC123_IN4/DAC_OUT1/SPI1_NSS_14") (pintype "passive"))
    )
    (net (code "25") (name "/PA5") (class "Default")
      (node (ref "S6") (pin "1") (pinfunction "1_1") (pintype "passive"))
      (node (ref "S6") (pin "4") (pinfunction "4_4") (pintype "passive"))
      (node (ref "S7") (pin "1") (pinfunction "1_1") (pintype "passive"))
      (node (ref "S7") (pin "4") (pinfunction "4_4") (pintype "passive"))
      (node (ref "S8") (pin "1") (pinfunction "1_1") (pintype "passive"))
      (node (ref "S8") (pin "4") (pinfunction "4_4") (pintype "passive"))
      (node (ref "S9") (pin "1") (pinfunction "1_1") (pintype "passive"))
      (node (ref "S9") (pin "4") (pinfunction "4_4") (pintype "passive"))
      (node (ref "U2") (pin "15") (pinfunction "PA5/ADC123_IN5/DAC_OUT2/SPI1_SCK_15") (pintype "passive"))
    )
    (net (code "26") (name "/PA6") (class "Default")
      (node (ref "S10") (pin "1") (pinfunction "1_1") (pintype "passive"))
      (node (ref "S10") (pin "4") (pinfunction "4_4") (pintype "passive"))
      (node (ref "S11") (pin "1") (pinfunction "1_1") (pintype "passive"))
      (node (ref "S11") (pin "4") (pinfunction "4_4") (pintype "passive"))
      (node (ref "S12") (pin "1") (pinfunction "1_1") (pintype "passive"))
      (node (ref "S12") (pin "4") (pinfunction "4_4") (pintype "passive"))
      (node (ref "S13") (pin "1") (pinfunction "1_1") (pintype "passive"))
      (node (ref "S13") (pin "4") (pinfunction "4_4") (pintype "passive"))
      (node (ref "U2") (pin "16") (pinfunction "PA6/ADC123_IN6/SPI1_MISO/T8T1BKIN/T3C1_16") (pintype "passive"))
    )
    (net (code "27") (name "/PA7") (class "Default")
      (node (ref "S14") (pin "1") (pinfunction "1_1") (pintype "passive"))
      (node (ref "S14") (pin "4") (pinfunction "4_4") (pintype "passive"))
      (node (ref "S15") (pin "1") (pinfunction "1_1") (pintype "passive"))
      (node (ref "S15") (pin "4") (pinfunction "4_4") (pintype "passive"))
      (node (ref "S16") (pin "1") (pinfunction "1_1") (pintype "passive"))
      (node (ref "S16") (pin "4") (pinfunction "4_4") (pintype "passive"))
      (node (ref "S17") (pin "1") (pinfunction "1_1") (pintype "passive"))
      (node (ref "S17") (pin "4") (pinfunction "4_4") (pintype "passive"))
      (node (ref "U2") (pin "17") (pinfunction "PA7/ADC123_IN7/SPI1_MOSI/T8C1N/T3C2/T1C1N_17") (pintype "passive"))
    )
    (net (code "28") (name "/PA10") (class "Default")
      (node (ref "R32") (pin "1") (pinfunction "1_1") (pintype "passive"))
      (node (ref "S18") (pin "1") (pinfunction "1_1") (pintype "passive"))
      (node (ref "S18") (pin "4") (pinfunction "4_4") (pintype "passive"))
      (node (ref "U2") (pin "31") (pinfunction "PA10/T1C3/USART1_Rx_31") (pintype "passive"))
    )
    (net (code "29") (name "/PB8") (class "Default")
      (node (ref "R28") (pin "1") (pinfunction "1_1") (pintype "passive"))
      (node (ref "S20") (pin "1") (pinfunction "1_1") (pintype "passive"))
      (node (ref "S20") (pin "4") (pinfunction "4_4") (pintype "passive"))
      (node (ref "U2") (pin "45") (pinfunction "PB8/SDIO_D4/I2C1_SCL/T4C3(7)/CAN_Rx_45") (pintype "passive"))
    )
    (net (code "30") (name "/PB9") (class "Default")
      (node (ref "R31") (pin "1") (pinfunction "1_1") (pintype "passive"))
      (node (ref "S19") (pin "1") (pinfunction "1_1") (pintype "passive"))
      (node (ref "S19") (pin "4") (pinfunction "4_4") (pintype "passive"))
      (node (ref "U2") (pin "46") (pinfunction "PB9/SDIO_D5/I2C1_SDA/T4C4/CAN_Tx_46") (pintype "passive"))
    )
    (net (code "31") (name "/PB15") (class "Default")
      (node (ref "D7") (pin "1") (pinfunction "A_1") (pintype "passive"))
      (node (ref "U2") (pin "28") (pinfunction "PB15/I2S2_SD/T1CH3N/SPI2_MOSI_28") (pintype "passive"))
    )
    (net (code "32") (name "/PWR") (class "Default")
      (node (ref "R10") (pin "1") (pinfunction "1_1") (pintype "passive"))
      (node (ref "U2") (pin "27") (pinfunction "PB14/T1CH2N/SPI2_MISO_27") (pintype "passive"))
    )
    (net (code "33") (name "/STM_RXD3") (class "Default")
      (node (ref "R34") (pin "1") (pinfunction "1_1") (pintype "passive"))
      (node (ref "RX2") (pin "2") (pinfunction "2_2") (pintype "passive"))
      (node (ref "U2") (pin "22") (pinfunction "PB11/USART3_Rx/I2C2_SDA/T2C4_22") (pintype "passive"))
      (node (ref "U4") (pin "1") (pinfunction "R_1") (pintype "passive"))
    )
    (net (code "34") (name "/STM_SWC") (class "Default")
      (node (ref "CON1") (pin "2") (pinfunction "2_2") (pintype "passive"))
      (node (ref "U2") (pin "37") (pinfunction "PA14/JTCK/SWCLK_37") (pintype "passive"))
    )
    (net (code "35") (name "/STM_SWD") (class "Default")
      (node (ref "CON1") (pin "3") (pinfunction "3_3") (pintype "passive"))
      (node (ref "U2") (pin "34") (pinfunction "PA13/JTMS/SWDIO_34") (pintype "passive"))
    )
    (net (code "36") (name "/STM_TXD3") (class "Default")
      (node (ref "R33") (pin "1") (pinfunction "1_1") (pintype "passive"))
      (node (ref "TX1") (pin "2") (pinfunction "2_2") (pintype "passive"))
      (node (ref "U2") (pin "21") (pinfunction "PB10/USART3_Tx/I2C2_SCL/T2C3_21") (pintype "passive"))
      (node (ref "U4") (pin "4") (pinfunction "D_4") (pintype "passive"))
    )
    (net (code "37") (name "/U_SCL") (class "Default")
      (node (ref "R29") (pin "2") (pinfunction "2_2") (pintype "passive"))
      (node (ref "U2") (pin "30") (pinfunction "PA9/T1C2/USART1_Tx_30") (pintype "passive"))
      (node (ref "U3") (pin "6") (pinfunction "SCL_6") (pintype "passive"))
    )
    (net (code "38") (name "/U_SDA") (class "Default")
      (node (ref "R30") (pin "2") (pinfunction "2_2") (pintype "passive"))
      (node (ref "U2") (pin "29") (pinfunction "PA8/T1C1/MCO_29") (pintype "passive"))
      (node (ref "U3") (pin "5") (pinfunction "SDA_5") (pintype "passive"))
    )
    (net (code "39") (name "EGND") (class "Default")
      (node (ref "EC1") (pin "1") (pinfunction "1_1") (pintype "passive"))
      (node (ref "EC2") (pin "1") (pinfunction "1_1") (pintype "passive"))
      (node (ref "EC3") (pin "1") (pinfunction "1_1") (pintype "passive"))
      (node (ref "EC4") (pin "1") (pinfunction "1_1") (pintype "passive"))
      (node (ref "EGND1") (pin "0") (pinfunction "0_0") (pintype "passive"))
      (node (ref "EGND2") (pin "0") (pinfunction "0_0") (pintype "passive"))
      (node (ref "EGND3") (pin "0") (pinfunction "0_0") (pintype "passive"))
      (node (ref "EGND4") (pin "0") (pinfunction "0_0") (pintype "passive"))
      (node (ref "ER1") (pin "1") (pinfunction "1_1") (pintype "passive"))
      (node (ref "ER2") (pin "1") (pinfunction "1_1") (pintype "passive"))
      (node (ref "ER3") (pin "1") (pinfunction "1_1") (pintype "passive"))
      (node (ref "ER4") (pin "1") (pinfunction "1_1") (pintype "passive"))
      (node (ref "J1") (pin "5") (pinfunction "SHELL_5") (pintype "passive"))
      (node (ref "J1") (pin "6") (pinfunction "SHELL_6") (pintype "passive"))
    )
    (net (code "40") (name "GND") (class "Default")
      (node (ref "C1") (pin "1") (pinfunction "1_1") (pintype "passive"))
      (node (ref "C12") (pin "2") (pinfunction "2_2") (pintype "passive"))
      (node (ref "C13") (pin "2") (pinfunction "2_2") (pintype "passive"))
      (node (ref "C2") (pin "1") (pinfunction "1_1") (pintype "passive"))
      (node (ref "C27") (pin "2") (pinfunction "2_2") (pintype "passive"))
      (node (ref "C28") (pin "2") (pinfunction "2_2") (pintype "passive"))
      (node (ref "C3") (pin "1") (pinfunction "1_1") (pintype "passive"))
      (node (ref "CN1") (pin "3") (pinfunction "GND_3") (pintype "passive"))
      (node (ref "D16") (pin "1") (pinfunction "A_1") (pintype "passive"))
      (node (ref "D17") (pin "1") (pinfunction "A_1") (pintype "passive"))
      (node (ref "D2") (pin "1") (pinfunction "A_1") (pintype "passive"))
      (node (ref "D3") (pin "1") (pinfunction "A_1") (pintype "passive"))
      (node (ref "D6") (pin "1") (pinfunction "A_1") (pintype "passive"))
      (node (ref "E2") (pin "2") (pinfunction "2_2") (pintype "passive"))
      (node (ref "E3") (pin "2") (pinfunction "2_2") (pintype "passive"))
      (node (ref "E5") (pin "2") (pinfunction "2_2") (pintype "passive"))
      (node (ref "E6") (pin "2") (pinfunction "2_2") (pintype "passive"))
      (node (ref "EC2") (pin "2") (pinfunction "2_2") (pintype "passive"))
      (node (ref "EC4") (pin "2") (pinfunction "2_2") (pintype "passive"))
      (node (ref "ER2") (pin "2") (pinfunction "2_2") (pintype "passive"))
      (node (ref "ER4") (pin "2") (pinfunction "2_2") (pintype "passive"))
      (node (ref "GND") (pin "1") (pinfunction "1_1") (pintype "passive"))
      (node (ref "J1") (pin "4") (pinfunction "VSS_4") (pintype "passive"))
      (node (ref "J2") (pin "2") (pinfunction "2_2") (pintype "power_in"))
      (node (ref "J2") (pin "3") (pinfunction "3_3") (pintype "power_in"))
      (node (ref "L3") (pin "1") (pinfunction "1_1") (pintype "passive"))
      (node (ref "R3") (pin "2") (pinfunction "2_2") (pintype "passive"))
      (node (ref "R40") (pin "1") (pinfunction "1_1") (pintype "passive"))
      (node (ref "R6") (pin "2") (pinfunction "2_2") (pintype "passive"))
      (node (ref "R9") (pin "2") (pinfunction "2_2") (pintype "passive"))
      (node (ref "RISET1") (pin "2") (pinfunction "2_2") (pintype "passive"))
      (node (ref "U1") (pin "1") (pinfunction "GND_1") (pintype "passive"))
      (node (ref "U4") (pin "5") (pinfunction "GND_5") (pintype "passive"))
    )
    (net (code "41") (name "Net-(C10-Pad2)") (class "Default")
      (node (ref "C10") (pin "2") (pinfunction "2_2") (pintype "passive"))
      (node (ref "E1") (pin "1") (pinfunction "1_1") (pintype "passive"))
      (node (ref "L2") (pin "2") (pinfunction "2_2") (pintype "passive"))
      (node (ref "R1") (pin "2") (pinfunction "2_2") (pintype "passive"))
    )
    (net (code "42") (name "Net-(C11-Pad1)") (class "Default")
      (node (ref "C11") (pin "1") (pinfunction "1_1") (pintype "passive"))
      (node (ref "R6") (pin "1") (pinfunction "1_1") (pintype "passive"))
    )
    (net (code "43") (name "Net-(C16-Pad1)") (class "Default")
      (node (ref "C16") (pin "1") (pinfunction "1_1") (pintype "passive"))
      (node (ref "P1") (pin "17") (pinfunction "17_17") (pintype "passive"))
      (node (ref "R17") (pin "2") (pinfunction "2_2") (pintype "passive"))
    )
    (net (code "44") (name "Net-(CN1-FB)") (class "Default")
      (node (ref "CN1") (pin "8") (pinfunction "FB_8") (pintype "passive"))
      (node (ref "Rx1") (pin "2") (pinfunction "2_2") (pintype "passive"))
    )
    (net (code "45") (name "Net-(CN1-ISET)") (class "Default")
      (node (ref "CN1") (pin "2") (pinfunction "ISET_2") (pintype "passive"))
      (node (ref "RISET1") (pin "1") (pinfunction "1_1") (pintype "passive"))
    )
    (net (code "46") (name "Net-(CN1-TEMP)") (class "Default")
      (node (ref "CN1") (pin "1") (pinfunction "TEMP_1") (pintype "passive"))
      (node (ref "R9") (pin "1") (pinfunction "1_1") (pintype "passive"))
    )
    (net (code "47") (name "Net-(CN1-VIN)") (class "Default")
      (node (ref "C13") (pin "1") (pinfunction "1_1") (pintype "passive"))
      (node (ref "CN1") (pin "4") (pinfunction "VIN_4") (pintype "passive"))
      (node (ref "D4") (pin "2") (pinfunction "K_2") (pintype "passive"))
      (node (ref "D6") (pin "2") (pinfunction "K_2") (pintype "passive"))
      (node (ref "R4") (pin "2") (pinfunction "2_2") (pintype "passive"))
    )
    (net (code "48") (name "Net-(D1-A)") (class "Default")
      (node (ref "D1") (pin "1") (pinfunction "A_1") (pintype "passive"))
      (node (ref "F1") (pin "2") (pinfunction "2_2") (pintype "passive"))
    )
    (net (code "49") (name "Net-(D4-A)") (class "Default")
      (node (ref "D4") (pin "1") (pinfunction "A_1") (pintype "passive"))
      (node (ref "F2") (pin "1") (pinfunction "1_1") (pintype "passive"))
    )
    (net (code "50") (name "Net-(D5-A)") (class "Default")
      (node (ref "D5") (pin "1") (pinfunction "A_1") (pintype "passive"))
      (node (ref "F3") (pin "2") (pinfunction "2_2") (pintype "passive"))
    )
    (net (code "51") (name "Net-(D5-K)") (class "Default")
      (node (ref "D5") (pin "2") (pinfunction "K_2") (pintype "passive"))
      (node (ref "Q1") (pin "2") (pinfunction "S_2") (pintype "passive"))
      (node (ref "R5") (pin "1") (pinfunction "1_1") (pintype "passive"))
    )
    (net (code "52") (name "Net-(D8-A)") (class "Default")
      (node (ref "D8") (pin "1") (pinfunction "A_1") (pintype "passive"))
      (node (ref "D9") (pin "1") (pinfunction "A_1") (pintype "passive"))
      (node (ref "R4") (pin "1") (pinfunction "1_1") (pintype "passive"))
    )
    (net (code "53") (name "Net-(D10-A)") (class "Default")
      (node (ref "D10") (pin "1") (pinfunction "A_1") (pintype "passive"))
      (node (ref "D11") (pin "1") (pinfunction "A_1") (pintype "passive"))
      (node (ref "Q2") (pin "3") (pinfunction "D_3") (pintype "passive"))
      (node (ref "R7") (pin "1") (pinfunction "1_1") (pintype "passive"))
    )
    (net (code "54") (name "Net-(D11-K)") (class "Default")
      (node (ref "D11") (pin "2") (pinfunction "K_2") (pintype "passive"))
      (node (ref "D7") (pin "2") (pinfunction "K_2") (pintype "passive"))
      (node (ref "R8") (pin "1") (pinfunction "1_1") (pintype "passive"))
      (node (ref "S1") (pin "1") (pinfunction "1_1") (pintype "passive"))
      (node (ref "S1") (pin "4") (pinfunction "4_4") (pintype "passive"))
    )
    (net (code "55") (name "Net-(D13-A)") (class "Default")
      (node (ref "D13") (pin "1") (pinfunction "A_1") (pintype "passive"))
      (node (ref "R13") (pin "1") (pinfunction "1_1") (pintype "passive"))
    )
    (net (code "56") (name "Net-(D14-A)") (class "Default")
      (node (ref "D14") (pin "1") (pinfunction "A_1") (pintype "passive"))
      (node (ref "R14") (pin "1") (pinfunction "1_1") (pintype "passive"))
    )
    (net (code "57") (name "Net-(J3-1)") (class "Default")
      (node (ref "J3") (pin "2") (pinfunction "1_2") (pintype "passive"))
      (node (ref "Q3") (pin "3") (pinfunction "C_3") (pintype "passive"))
    )
    (net (code "58") (name "Net-(Q1-G)") (class "Default")
      (node (ref "Q1") (pin "1") (pinfunction "G_1") (pintype "passive"))
      (node (ref "R5") (pin "2") (pinfunction "2_2") (pintype "passive"))
      (node (ref "R7") (pin "2") (pinfunction "2_2") (pintype "passive"))
    )
    (net (code "59") (name "Net-(Q2-G)") (class "Default")
      (node (ref "Q2") (pin "1") (pinfunction "G_1") (pintype "passive"))
      (node (ref "R10") (pin "2") (pinfunction "2_2") (pintype "passive"))
      (node (ref "R11") (pin "2") (pinfunction "2_2") (pintype "passive"))
    )
    (net (code "60") (name "Net-(Q3-B)") (class "Default")
      (node (ref "Q3") (pin "1") (pinfunction "B_1") (pintype "passive"))
      (node (ref "R26") (pin "2") (pinfunction "2_2") (pintype "passive"))
      (node (ref "R27") (pin "2") (pinfunction "2_2") (pintype "passive"))
    )
    (net (code "61") (name "Net-(Q4-B)") (class "Default")
      (node (ref "Q4") (pin "1") (pinfunction "B_1") (pintype "passive"))
      (node (ref "R42") (pin "2") (pinfunction "2_2") (pintype "passive"))
    )
    (net (code "62") (name "Net-(R12-TAP)") (class "Default")
      (node (ref "P1") (pin "3") (pinfunction "3_3") (pintype "passive"))
      (node (ref "R12") (pin "2") (pinfunction "TAP_2") (pintype "passive"))
    )
    (net (code "63") (name "Net-(R36-Pad2)") (class "Default")
      (node (ref "R36") (pin "2") (pinfunction "2_2") (pintype "passive"))
      (node (ref "RX2") (pin "1") (pinfunction "1_1") (pintype "passive"))
    )
    (net (code "64") (name "Net-(R38-Pad2)") (class "Default")
      (node (ref "R38") (pin "2") (pinfunction "2_2") (pintype "passive"))
      (node (ref "TX1") (pin "1") (pinfunction "1_1") (pintype "passive"))
    )
    (net (code "65") (name "Net-(U1-IN)") (class "Default")
      (node (ref "C2") (pin "2") (pinfunction "2_2") (pintype "passive"))
      (node (ref "E2") (pin "1") (pinfunction "1_1") (pintype "passive"))
      (node (ref "E6") (pin "1") (pinfunction "1_1") (pintype "passive"))
      (node (ref "L1") (pin "2") (pinfunction "2_2") (pintype "passive"))
      (node (ref "U1") (pin "3") (pinfunction "IN_3") (pintype "passive"))
    )
    (net (code "66") (name "Net-(U2-OSC_IN)") (class "Default")
      (node (ref "C17") (pin "1") (pinfunction "1_1") (pintype "passive"))
      (node (ref "R23") (pin "2") (pinfunction "2_2") (pintype "passive"))
      (node (ref "U2") (pin "5") (pinfunction "OSC_IN_5") (pintype "passive"))
      (node (ref "Y1") (pin "1") (pinfunction "OSC1_1") (pintype "passive"))
    )
    (net (code "67") (name "Net-(U2-OSC_OUT)") (class "Default")
      (node (ref "C18") (pin "1") (pinfunction "1_1") (pintype "passive"))
      (node (ref "R23") (pin "1") (pinfunction "1_1") (pintype "passive"))
      (node (ref "U2") (pin "6") (pinfunction "OSC_OUT_6") (pintype "passive"))
      (node (ref "Y1") (pin "2") (pinfunction "OSC2_2") (pintype "passive"))
    )
    (net (code "68") (name "Net-(U4-A)") (class "Default")
      (node (ref "R35") (pin "1") (pinfunction "1_1") (pintype "passive"))
      (node (ref "R39") (pin "2") (pinfunction "2_2") (pintype "passive"))
      (node (ref "R41") (pin "1") (pinfunction "1_1") (pintype "passive"))
      (node (ref "U4") (pin "6") (pinfunction "A_6") (pintype "passive"))
    )
    (net (code "69") (name "Net-(U4-B)") (class "Default")
      (node (ref "R37") (pin "2") (pinfunction "2_2") (pintype "passive"))
      (node (ref "R40") (pin "2") (pinfunction "2_2") (pintype "passive"))
      (node (ref "R41") (pin "2") (pinfunction "2_2") (pintype "passive"))
      (node (ref "U4") (pin "7") (pinfunction "B_7") (pintype "passive"))
    )
    (net (code "70") (name "VCC-3.3V") (class "Default")
      (node (ref "C3") (pin "2") (pinfunction "2_2") (pintype "passive"))
      (node (ref "D3") (pin "2") (pinfunction "K_2") (pintype "passive"))
      (node (ref "E3") (pin "1") (pinfunction "1_1") (pintype "passive"))
      (node (ref "L2") (pin "1") (pinfunction "1_1") (pintype "passive"))
      (node (ref "U1") (pin "2") (pinfunction "OUT_2") (pintype "passive"))
    )
    (net (code "71") (name "VCC-5V") (class "Default")
      (node (ref "C1") (pin "2") (pinfunction "2_2") (pintype "passive"))
      (node (ref "C27") (pin "1") (pinfunction "1_1") (pintype "passive"))
      (node (ref "C28") (pin "1") (pinfunction "1_1") (pintype "passive"))
      (node (ref "D1") (pin "2") (pinfunction "K_2") (pintype "passive"))
      (node (ref "D2") (pin "2") (pinfunction "K_2") (pintype "passive"))
      (node (ref "E5") (pin "1") (pinfunction "1_1") (pintype "passive"))
      (node (ref "L1") (pin "1") (pinfunction "1_1") (pintype "passive"))
      (node (ref "Q1") (pin "3") (pinfunction "D_3") (pintype "passive"))
      (node (ref "R33") (pin "2") (pinfunction "2_2") (pintype "passive"))
      (node (ref "R34") (pin "2") (pinfunction "2_2") (pintype "passive"))
      (node (ref "R35") (pin "2") (pinfunction "2_2") (pintype "passive"))
      (node (ref "U4") (pin "8") (pinfunction "VCC_8") (pintype "passive"))
      (node (ref "VCC-5V") (pin "1") (pinfunction "1_1") (pintype "passive"))
    )
    (net (code "72") (name "VDD") (class "Default")
      (node (ref "C20") (pin "2") (pinfunction "2_2") (pintype "passive"))
      (node (ref "C21") (pin "2") (pinfunction "2_2") (pintype "passive"))
      (node (ref "C22") (pin "2") (pinfunction "2_2") (pintype "passive"))
      (node (ref "C23") (pin "2") (pinfunction "2_2") (pintype "passive"))
      (node (ref "C24") (pin "2") (pinfunction "2_2") (pintype "passive"))
      (node (ref "C25") (pin "2") (pinfunction "2_2") (pintype "passive"))
      (node (ref "C26") (pin "2") (pinfunction "2_2") (pintype "passive"))
      (node (ref "C4") (pin "1") (pinfunction "1_1") (pintype "passive"))
      (node (ref "C5") (pin "2") (pinfunction "2_2") (pintype "passive"))
      (node (ref "C6") (pin "2") (pinfunction "2_2") (pintype "passive"))
      (node (ref "C7") (pin "2") (pinfunction "2_2") (pintype "passive"))
      (node (ref "C8") (pin "2") (pinfunction "2_2") (pintype "passive"))
      (node (ref "C9") (pin "2") (pinfunction "2_2") (pintype "passive"))
      (node (ref "CON1") (pin "4") (pinfunction "4_4") (pintype "passive"))
      (node (ref "E4") (pin "1") (pinfunction "1_1") (pintype "passive"))
      (node (ref "J3") (pin "1") (pinfunction "0_1") (pintype "passive"))
      (node (ref "R1") (pin "1") (pinfunction "1_1") (pintype "passive"))
      (node (ref "R13") (pin "2") (pinfunction "2_2") (pintype "passive"))
      (node (ref "R14") (pin "2") (pinfunction "2_2") (pintype "passive"))
      (node (ref "R15") (pin "1") (pinfunction "1_1") (pintype "passive"))
      (node (ref "R18") (pin "2") (pinfunction "2_2") (pintype "passive"))
      (node (ref "R19") (pin "2") (pinfunction "2_2") (pintype "passive"))
      (node (ref "R20") (pin "2") (pinfunction "2_2") (pintype "passive"))
      (node (ref "R22") (pin "2") (pinfunction "2_2") (pintype "passive"))
      (node (ref "R25") (pin "2") (pinfunction "2_2") (pintype "passive"))
      (node (ref "R28") (pin "2") (pinfunction "2_2") (pintype "passive"))
      (node (ref "R29") (pin "1") (pinfunction "1_1") (pintype "passive"))
      (node (ref "R30") (pin "1") (pinfunction "1_1") (pintype "passive"))
      (node (ref "R31") (pin "2") (pinfunction "2_2") (pintype "passive"))
      (node (ref "R32") (pin "2") (pinfunction "2_2") (pintype "passive"))
      (node (ref "R36") (pin "1") (pinfunction "1_1") (pintype "passive"))
      (node (ref "R38") (pin "1") (pinfunction "1_1") (pintype "passive"))
      (node (ref "R8") (pin "2") (pinfunction "2_2") (pintype "passive"))
      (node (ref "U2") (pin "1") (pinfunction "VBAT_1") (pintype "passive"))
      (node (ref "U2") (pin "24") (pinfunction "VDD_1_24") (pintype "passive"))
      (node (ref "U2") (pin "36") (pinfunction "VDD_2_36") (pintype "passive"))
      (node (ref "U2") (pin "48") (pinfunction "VDD_3_48") (pintype "passive"))
      (node (ref "U2") (pin "9") (pinfunction "VDDA_9") (pintype "passive"))
      (node (ref "U3") (pin "8") (pinfunction "VCC_8") (pintype "passive"))
      (node (ref "VDD") (pin "1") (pinfunction "1_1") (pintype "passive"))
    )
    (net (code "73") (name "VSS") (class "Default")
      (node (ref "C10") (pin "1") (pinfunction "1_1") (pintype "passive"))
      (node (ref "C14") (pin "2") (pinfunction "2_2") (pintype "passive"))
      (node (ref "C15") (pin "2") (pinfunction "2_2") (pintype "passive"))
      (node (ref "C16") (pin "2") (pinfunction "2_2") (pintype "passive"))
      (node (ref "C17") (pin "2") (pinfunction "2_2") (pintype "passive"))
      (node (ref "C18") (pin "2") (pinfunction "2_2") (pintype "passive"))
      (node (ref "C19") (pin "1") (pinfunction "1_1") (pintype "passive"))
      (node (ref "C20") (pin "1") (pinfunction "1_1") (pintype "passive"))
      (node (ref "C21") (pin "1") (pinfunction "1_1") (pintype "passive"))
      (node (ref "C22") (pin "1") (pinfunction "1_1") (pintype "passive"))
      (node (ref "C23") (pin "1") (pinfunction "1_1") (pintype "passive"))
      (node (ref "C24") (pin "1") (pinfunction "1_1") (pintype "passive"))
      (node (ref "C25") (pin "1") (pinfunction "1_1") (pintype "passive"))
      (node (ref "C26") (pin "1") (pinfunction "1_1") (pintype "passive"))
      (node (ref "C4") (pin "2") (pinfunction "2_2") (pintype "passive"))
      (node (ref "C5") (pin "1") (pinfunction "1_1") (pintype "passive"))
      (node (ref "C6") (pin "1") (pinfunction "1_1") (pintype "passive"))
      (node (ref "C7") (pin "1") (pinfunction "1_1") (pintype "passive"))
      (node (ref "C8") (pin "1") (pinfunction "1_1") (pintype "passive"))
      (node (ref "C9") (pin "1") (pinfunction "1_1") (pintype "passive"))
      (node (ref "CON1") (pin "1") (pinfunction "1_1") (pintype "passive"))
      (node (ref "D14") (pin "2") (pinfunction "K_2") (pintype "passive"))
      (node (ref "E1") (pin "2") (pinfunction "2_2") (pintype "passive"))
      (node (ref "E4") (pin "2") (pinfunction "2_2") (pintype "passive"))
      (node (ref "EC1") (pin "2") (pinfunction "2_2") (pintype "passive"))
      (node (ref "EC3") (pin "2") (pinfunction "2_2") (pintype "passive"))
      (node (ref "ER1") (pin "2") (pinfunction "2_2") (pintype "passive"))
      (node (ref "ER3") (pin "2") (pinfunction "2_2") (pintype "passive"))
      (node (ref "L3") (pin "2") (pinfunction "2_2") (pintype "passive"))
      (node (ref "P1") (pin "1") (pinfunction "1_1") (pintype "passive"))
      (node (ref "P1") (pin "15") (pinfunction "15_15") (pintype "passive"))
      (node (ref "P1") (pin "20") (pinfunction "20_20") (pintype "passive"))
      (node (ref "Q2") (pin "2") (pinfunction "S_2") (pintype "passive"))
      (node (ref "Q3") (pin "2") (pinfunction "E_2") (pintype "passive"))
      (node (ref "R11") (pin "1") (pinfunction "1_1") (pintype "passive"))
      (node (ref "R12") (pin "1") (pinfunction "TOP_1") (pintype "passive"))
      (node (ref "R21") (pin "1") (pinfunction "1_1") (pintype "passive"))
      (node (ref "R24") (pin "1") (pinfunction "1_1") (pintype "passive"))
      (node (ref "R27") (pin "1") (pinfunction "1_1") (pintype "passive"))
      (node (ref "S1") (pin "2") (pinfunction "2_2") (pintype "passive"))
      (node (ref "S1") (pin "3") (pinfunction "3_3") (pintype "passive"))
      (node (ref "S18") (pin "2") (pinfunction "2_2") (pintype "passive"))
      (node (ref "S18") (pin "3") (pinfunction "3_3") (pintype "passive"))
      (node (ref "S19") (pin "2") (pinfunction "2_2") (pintype "passive"))
      (node (ref "S19") (pin "3") (pinfunction "3_3") (pintype "passive"))
      (node (ref "S20") (pin "2") (pinfunction "2_2") (pintype "passive"))
      (node (ref "S20") (pin "3") (pinfunction "3_3") (pintype "passive"))
      (node (ref "U2") (pin "23") (pinfunction "VSS_1_23") (pintype "passive"))
      (node (ref "U2") (pin "35") (pinfunction "VSS_2_35") (pintype "passive"))
      (node (ref "U2") (pin "47") (pinfunction "VSS_3_47") (pintype "passive"))
      (node (ref "U2") (pin "8") (pinfunction "VSSA_8") (pintype "passive"))
      (node (ref "U3") (pin "1") (pinfunction "A0_1") (pintype "passive"))
      (node (ref "U3") (pin "2") (pinfunction "A1_2") (pintype "passive"))
      (node (ref "U3") (pin "3") (pinfunction "A2_3") (pintype "passive"))
      (node (ref "U3") (pin "4") (pinfunction "VSS_4") (pintype "passive"))
      (node (ref "U3") (pin "7") (pinfunction "WP_7") (pintype "passive"))
      (node (ref "VSS") (pin "1") (pinfunction "1_1") (pintype "passive"))
      (node (ref "key1") (pin "2") (pinfunction "2_2") (pintype "passive"))
    )
    (net (code "74") (name "VUSB") (class "Default")
      (node (ref "F1") (pin "1") (pinfunction "1_1") (pintype "passive"))
      (node (ref "F2") (pin "2") (pinfunction "2_2") (pintype "passive"))
      (node (ref "J1") (pin "1") (pinfunction "VCC_1") (pintype "passive"))
      (node (ref "J2") (pin "1") (pinfunction "1_1") (pintype "power_in"))
      (node (ref "R16") (pin "1") (pinfunction "1_1") (pintype "passive"))
      (node (ref "VUSB") (pin "1") (pinfunction "1_1") (pintype "passive"))
    )
    (net (code "75") (name "V_BAT") (class "Default")
      (node (ref "C11") (pin "2") (pinfunction "2_2") (pintype "passive"))
      (node (ref "C12") (pin "1") (pinfunction "1_1") (pintype "passive"))
      (node (ref "CN1") (pin "5") (pinfunction "BAT_5") (pintype "passive"))
      (node (ref "F3") (pin "1") (pinfunction "1_1") (pintype "passive"))
      (node (ref "R2") (pin "1") (pinfunction "1_1") (pintype "passive"))
      (node (ref "Rx1") (pin "1") (pinfunction "1_1") (pintype "passive"))
      (node (ref "V_BAT") (pin "1") (pinfunction "1_1") (pintype "passive"))
    )
    (net (code "76") (name "unconnected-(P1-Pad7)") (class "Default")
      (node (ref "P1") (pin "7") (pinfunction "7_7") (pintype "passive"))
    )
    (net (code "77") (name "unconnected-(P1-Pad8)") (class "Default")
      (node (ref "P1") (pin "8") (pinfunction "8_8") (pintype "passive"))
    )
    (net (code "78") (name "unconnected-(P1-Pad9)") (class "Default")
      (node (ref "P1") (pin "9") (pinfunction "9_9") (pintype "passive"))
    )
    (net (code "79") (name "unconnected-(P1-Pad10)") (class "Default")
      (node (ref "P1") (pin "10") (pinfunction "10_10") (pintype "passive"))
    )
    (net (code "80") (name "unconnected-(P1-Pad11)") (class "Default")
      (node (ref "P1") (pin "11") (pinfunction "11_11") (pintype "passive"))
    )
    (net (code "81") (name "unconnected-(P1-Pad12)") (class "Default")
      (node (ref "P1") (pin "12") (pinfunction "12_12") (pintype "passive"))
    )
    (net (code "82") (name "unconnected-(P1-Pad13)") (class "Default")
      (node (ref "P1") (pin "13") (pinfunction "13_13") (pintype "passive"))
    )
    (net (code "83") (name "unconnected-(P1-Pad14)") (class "Default")
      (node (ref "P1") (pin "14") (pinfunction "14_14") (pintype "passive"))
    )
    (net (code "84") (name "unconnected-(P1-Pad16)") (class "Default")
      (node (ref "P1") (pin "16") (pinfunction "16_16") (pintype "passive"))
    )
    (net (code "85") (name "unconnected-(P1-Pad18)") (class "Default")
      (node (ref "P1") (pin "18") (pinfunction "18_18") (pintype "passive"))
    )
    (net (code "86") (name "unconnected-(U2-PB6{slash}I2C1_SCL{slash}T4C1{slash}USART1_Tx-Pad42)") (class "Default")
      (node (ref "U2") (pin "42") (pinfunction "PB6/I2C1_SCL/T4C1/USART1_Tx_42") (pintype "passive"))
    )
    (net (code "87") (name "unconnected-(U2-PC13-TAMPER-RTC-Pad2)") (class "Default")
      (node (ref "U2") (pin "2") (pinfunction "PC13-TAMPER-RTC_2") (pintype "passive"))
    )
    (net (code "88") (name "unconnected-(U2-PC14-OSC32_IN-Pad3)") (class "Default")
      (node (ref "U2") (pin "3") (pinfunction "PC14-OSC32_IN_3") (pintype "passive"))
    )
    (net (code "89") (name "unconnected-(U2-PC15-OSC32_OUT-Pad4)") (class "Default")
      (node (ref "U2") (pin "4") (pinfunction "PC15-OSC32_OUT_4") (pintype "passive"))
    )
  )
)
